# PowerSupply5V.net
KiCad netlist of a schematic drawn in Altium Designer
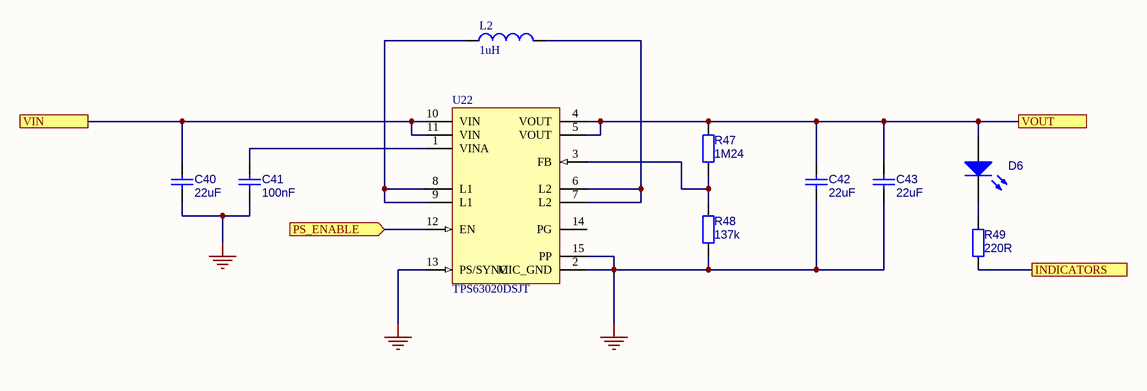
[diagram p0: PowerSupply5V.SchDoc]

(export (version "E")
  (design (tool "Eeschema 10.0.6"))
  (components
    (comp (ref "C40")
      (value "22uF")
      (footprint "0603_CAP UF HD")
      (description "Capacitor")
      (fields (field (name "MANUFACTURER") "MuRata"))
      (libsource (lib "MEGAphone") (part "Cap"))
    )
    (comp (ref "C41")
      (value "100nF")
      (footprint "0603_CAP UF HD")
      (description "Capacitor")
      (libsource (lib "MEGAphone") (part "Cap"))
    )
    (comp (ref "C42")
      (value "22uF")
      (footprint "0603_CAP UF HD")
      (description "Capacitor")
      (fields (field (name "MANUFACTURER") "MuRata"))
      (libsource (lib "MEGAphone") (part "Cap"))
    )
    (comp (ref "C43")
      (value "22uF")
      (footprint "0603_CAP UF HD")
      (description "Capacitor")
      (fields (field (name "MANUFACTURER") "MuRata"))
      (libsource (lib "MEGAphone") (part "Cap"))
    )
    (comp (ref "D6")
      (value "~")
      (footprint "LED 3mm Red")
      (description "LED")
      (libsource (lib "MEGAphone") (part "LED"))
    )
    (comp (ref "L2")
      (value "1uH")
      (footprint "252012")
      (description "Inductor")
      (fields (field (name "MANUFACTURER") "Samsung Electro-Mechanics"))
      (libsource (lib "MEGAphone") (part "Inductor_1"))
    )
    (comp (ref "R47")
      (value "1M24")
      (footprint "0603-RESISTOR HD")
      (description "Resistor")
      (libsource (lib "MEGAphone") (part "Resistor"))
    )
    (comp (ref "R48")
      (value "137k")
      (footprint "0603-RESISTOR HD")
      (description "Resistor")
      (libsource (lib "MEGAphone") (part "Resistor"))
    )
    (comp (ref "R49")
      (value "220R")
      (footprint "0603-RESISTOR HD")
      (description "Resistor")
      (libsource (lib "MEGAphone") (part "Resistor"))
    )
    (comp (ref "U22")
      (value "TPS63020DSJT")
      (footprint "DSJ14-4000X1580TP_V")
      (fields (field (name "MANUFACTURER") "Texas Instruments"))
      (libsource (lib "MEGAphone") (part "TPS63020DSJ14"))
    )
  )
  (nets
    (net (code "1") (name "/INDICATORS") (class "Default")
      (node (ref "R49") (pin "2") (pinfunction "2_2") (pintype "passive"))
    )
    (net (code "2") (name "/PS_ENABLE") (class "Default")
      (node (ref "U22") (pin "12") (pinfunction "EN_12") (pintype "input"))
    )
    (net (code "3") (name "/VIN") (class "Default")
      (node (ref "C40") (pin "1") (pinfunction "1_1") (pintype "passive"))
      (node (ref "U22") (pin "10") (pinfunction "VIN_10") (pintype "power_in"))
      (node (ref "U22") (pin "11") (pinfunction "VIN_11") (pintype "power_in"))
    )
    (net (code "4") (name "/VOUT") (class "Default")
      (node (ref "C42") (pin "1") (pinfunction "1_1") (pintype "passive"))
      (node (ref "C43") (pin "1") (pinfunction "1_1") (pintype "passive"))
      (node (ref "D6") (pin "A") (pinfunction "A_A") (pintype "passive"))
      (node (ref "R47") (pin "1") (pinfunction "1_1") (pintype "passive"))
      (node (ref "U22") (pin "4") (pinfunction "VOUT_4") (pintype "power_in"))
      (node (ref "U22") (pin "5") (pinfunction "VOUT_5") (pintype "power_in"))
    )
    (net (code "5") (name "GND") (class "Default")
      (node (ref "C40") (pin "2") (pinfunction "2_2") (pintype "passive"))
      (node (ref "C41") (pin "2") (pinfunction "2_2") (pintype "passive"))
      (node (ref "C42") (pin "2") (pinfunction "2_2") (pintype "passive"))
      (node (ref "C43") (pin "2") (pinfunction "2_2") (pintype "passive"))
      (node (ref "R48") (pin "2") (pinfunction "2_2") (pintype "passive"))
      (node (ref "U22") (pin "13") (pinfunction "PS/SYNC_13") (pintype "input"))
      (node (ref "U22") (pin "15") (pinfunction "PP_15") (pintype "power_in"))
      (node (ref "U22") (pin "2") (pinfunction "MIC_GND_2") (pintype "power_in"))
    )
    (net (code "6") (name "Net-(D6-PadK)") (class "Default")
      (node (ref "D6") (pin "K") (pinfunction "K_K") (pintype "passive"))
      (node (ref "R49") (pin "1") (pinfunction "1_1") (pintype "passive"))
    )
    (net (code "7") (name "Net-(L2-Pad1)") (class "Default")
      (node (ref "L2") (pin "1") (pinfunction "1_1") (pintype "passive"))
      (node (ref "U22") (pin "8") (pinfunction "L1_8") (pintype "passive"))
      (node (ref "U22") (pin "9") (pinfunction "L1_9") (pintype "passive"))
    )
    (net (code "8") (name "Net-(L2-Pad2)") (class "Default")
      (node (ref "L2") (pin "2") (pinfunction "2_2") (pintype "passive"))
      (node (ref "U22") (pin "6") (pinfunction "L2_6") (pintype "passive"))
      (node (ref "U22") (pin "7") (pinfunction "L2_7") (pintype "passive"))
    )
    (net (code "9") (name "Net-(U22-FB)") (class "Default")
      (node (ref "R47") (pin "2") (pinfunction "2_2") (pintype "passive"))
      (node (ref "R48") (pin "1") (pinfunction "1_1") (pintype "passive"))
      (node (ref "U22") (pin "3") (pinfunction "FB_3") (pintype "input"))
    )
    (net (code "10") (name "Net-(U22-VINA)") (class "Default")
      (node (ref "C41") (pin "1") (pinfunction "1_1") (pintype "passive"))
      (node (ref "U22") (pin "1") (pinfunction "VINA_1") (pintype "power_in"))
    )
    (net (code "11") (name "unconnected-(U22-PG-Pad14)") (class "Default")
      (node (ref "U22") (pin "14") (pinfunction "PG_14") (pintype "open_collector"))
    )
  )
)
